# MCU.net
KiCad netlist of a schematic drawn in Altium Designer
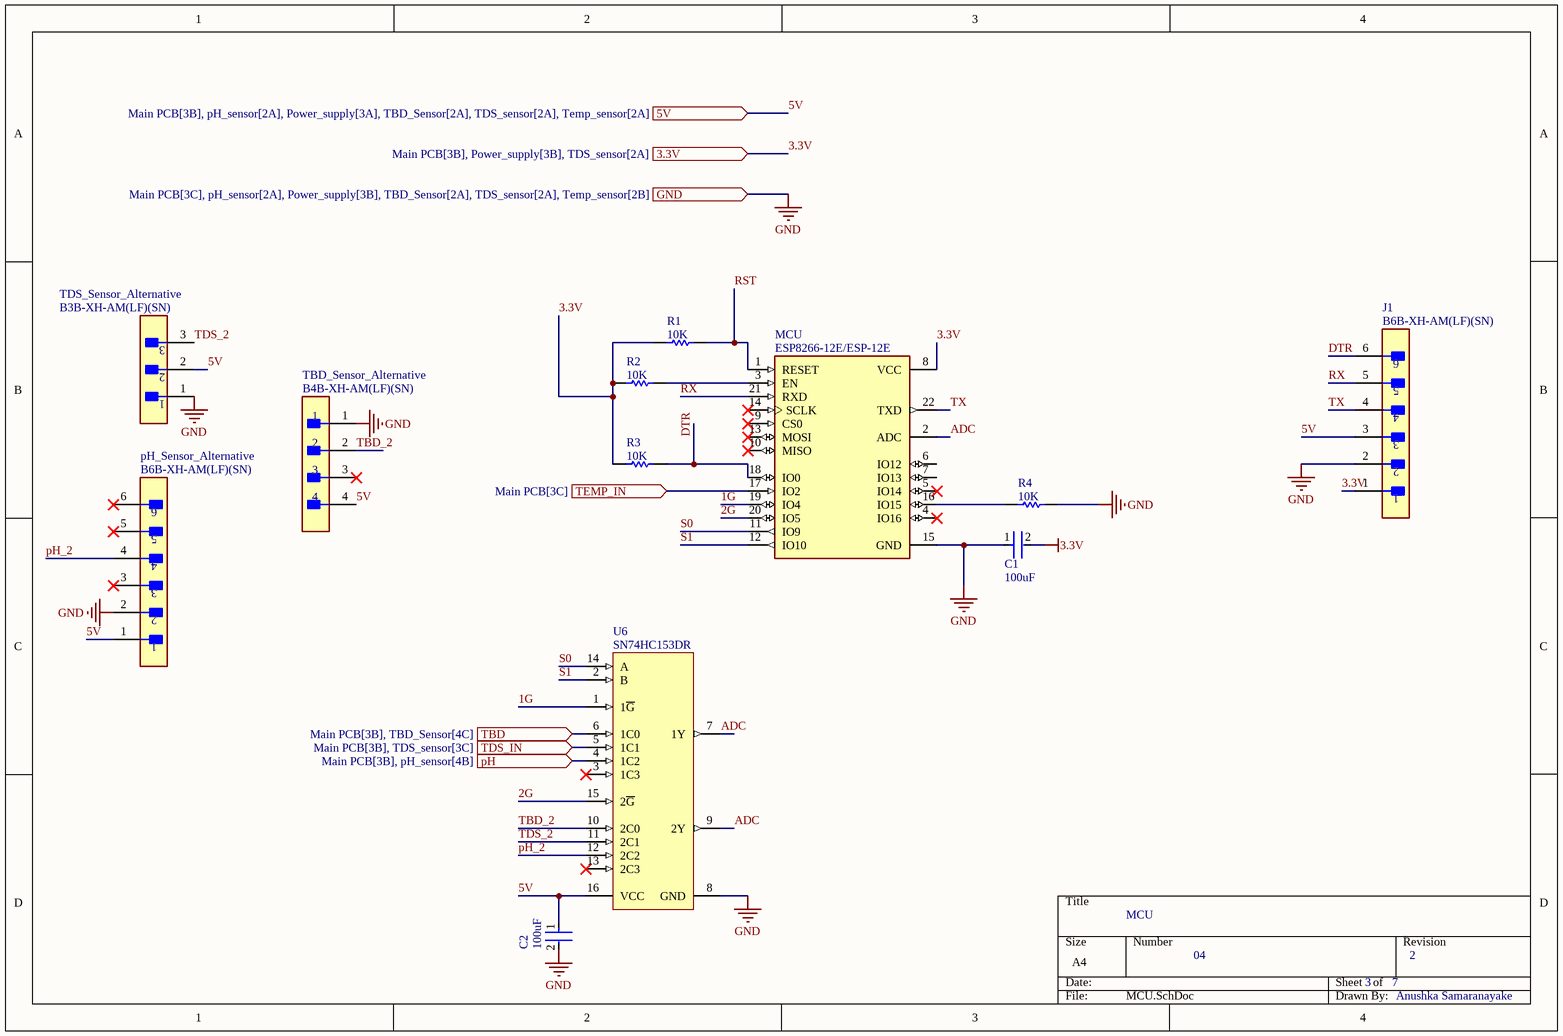
[diagram p0: MCU.SchDoc]

(export (version "E")
  (design (tool "Eeschema 10.0.6"))
  (components
    (comp (ref "C1")
      (value "100uF")
      (footprint "FP-GRM31M-0_15-IPC_A")
      (fields (field (name "VOLTAGE") "50V") (field (name "TOLERANCE") "5%"))
      (libsource (lib "Altium Content Vault") (part "b4654b650e69147ec39a6b967a45e02"))
    )
    (comp (ref "C2")
      (value "100uF")
      (footprint "FP-CL31-IPC_B")
      (description "Cap Ceramic 100nF 50V X7R ±10% SMD 1206 +125°C Embossed T/R")
      (fields (field (name "VOLTAGE") "50V") (field (name "TOLERANCE") "10%"))
      (libsource (lib "Altium Content Vault") (part "b4654b650e69147ec39a6b967a45e02"))
    )
    (comp (ref "J1")
      (value "B6B-XH-AM(LF)(SN)")
      (footprint "FP-B6B-XH-AM_LF_SN-MFG")
      (description "CONN HEADER VERT 6POS 2.5MM")
      (libsource (lib "Altium Content Vault") (part "f2cb566baf1c37ab5a3b8e90bbeafd6"))
    )
    (comp (ref "MCU")
      (value "ESP8266-12E/ESP-12E")
      (footprint "XCVR_ESP8266-12E/ESP-12E")
      (fields (field (name "MF") "AI-Thinker"))
      (libsource (lib "ESP8266-12E_ESP-12E") (part "ESP8266-12E/ESP-12E"))
    )
    (comp (ref "pH_Sensor_Alternative")
      (value "B6B-XH-AM(LF)(SN)")
      (footprint "FP-B6B-XH-AM_LF_SN-MFG")
      (description "CONN HEADER VERT 6POS 2.5MM")
      (libsource (lib "Altium Content Vault") (part "f2cb566baf1c37ab5a3b8e90bbeafd6"))
    )
    (comp (ref "R1")
      (value "10K")
      (footprint "RESC3216X70X50LL20T25")
      (fields (field (name "MANUFACTURER") "Panasonic") (field (name "PART NUMBER") "ERA8AEB103V"))
      (libsource (lib "Altium Content Vault") (part "RES"))
    )
    (comp (ref "R2")
      (value "10K")
      (footprint "RESC3216X70X50LL20T25")
      (fields (field (name "MANUFACTURER") "Panasonic") (field (name "PART NUMBER") "ERA8AEB103V"))
      (libsource (lib "Altium Content Vault") (part "RES"))
    )
    (comp (ref "R3")
      (value "10K")
      (footprint "RESC3216X70X50LL20T25")
      (fields (field (name "MANUFACTURER") "Panasonic") (field (name "PART NUMBER") "ERA8AEB103V"))
      (libsource (lib "Altium Content Vault") (part "RES"))
    )
    (comp (ref "R4")
      (value "10K")
      (footprint "RESC3216X70X50LL20T25")
      (fields (field (name "MANUFACTURER") "Panasonic") (field (name "PART NUMBER") "ERA8AEB103V"))
      (libsource (lib "Altium Content Vault") (part "RES"))
    )
    (comp (ref "TBD_Sensor_Alternative")
      (value "B4B-XH-AM(LF)(SN)")
      (footprint "FP-B4B-XH-AM_LF_SN-MFG")
      (description "CONN HEADER VERT 4POS 2.5MM")
      (libsource (lib "Altium Content Vault") (part "299a8cea1bdcbc3624fe62c390fa72c"))
    )
    (comp (ref "TDS_Sensor_Alternative")
      (value "B3B-XH-AM(LF)(SN)")
      (footprint "FP-B3B-XH-AM_LF_SN-MFG")
      (description "CONN HEADER VERT 3POS 2.5MM")
      (libsource (lib "Altium Content Vault") (part "0d3f023dd272f625e17a2be33dea85f"))
    )
    (comp (ref "U6")
      (value "SN74HC153DR")
      (footprint "D0016A_L")
      (description "Dual 4-Line To 1-Line Data Selectors/Multiplexers, D0016A, LARGE T&R")
      (fields
        (field (name "MANUFACTURER") "Texas Instruments")
        (field (name "GENERIC PART NUMBER") "SN74HC153")
      )
      (libsource (lib "Altium Content Vault") (part "TI-XXXXXXX153-16"))
    )
  )
  (nets
    (net (code "1") (name "/1G") (class "Default")
      (node (ref "MCU") (pin "19") (pinfunction "IO4_19") (pintype "bidirectional"))
      (node (ref "U6") (pin "1") (pinfunction "1~{G}_1") (pintype "input"))
    )
    (net (code "2") (name "/2G") (class "Default")
      (node (ref "MCU") (pin "20") (pinfunction "IO5_20") (pintype "bidirectional"))
      (node (ref "U6") (pin "15") (pinfunction "2~{G}_15") (pintype "input"))
    )
    (net (code "3") (name "/5V") (class "Default")
      (node (ref "C2") (pin "1") (pinfunction "1_1") (pintype "passive"))
      (node (ref "J1") (pin "3") (pinfunction "3_3") (pintype "passive"))
      (node (ref "TBD_Sensor_Alternative") (pin "4") (pinfunction "4_4") (pintype "passive"))
      (node (ref "TDS_Sensor_Alternative") (pin "2") (pinfunction "2_2") (pintype "passive"))
      (node (ref "U6") (pin "16") (pinfunction "VCC_16") (pintype "passive"))
      (node (ref "pH_Sensor_Alternative") (pin "1") (pinfunction "1_1") (pintype "passive"))
    )
    (net (code "4") (name "/ADC") (class "Default")
      (node (ref "MCU") (pin "2") (pinfunction "ADC_2") (pintype "passive"))
      (node (ref "U6") (pin "7") (pinfunction "1Y_7") (pintype "output"))
      (node (ref "U6") (pin "9") (pinfunction "2Y_9") (pintype "output"))
    )
    (net (code "5") (name "/DTR") (class "Default")
      (node (ref "J1") (pin "6") (pinfunction "6_6") (pintype "passive"))
      (node (ref "MCU") (pin "18") (pinfunction "IO0_18") (pintype "bidirectional"))
      (node (ref "R3") (pin "1") (pinfunction "1_1") (pintype "passive"))
    )
    (net (code "6") (name "/RST") (class "Default")
      (node (ref "MCU") (pin "1") (pinfunction "RESET_1") (pintype "input"))
      (node (ref "R1") (pin "1") (pinfunction "1_1") (pintype "passive"))
    )
    (net (code "7") (name "/RX") (class "Default")
      (node (ref "J1") (pin "5") (pinfunction "5_5") (pintype "passive"))
      (node (ref "MCU") (pin "21") (pinfunction "RXD_21") (pintype "input"))
    )
    (net (code "8") (name "/S0") (class "Default")
      (node (ref "MCU") (pin "11") (pinfunction "IO9_11") (pintype "output"))
      (node (ref "U6") (pin "14") (pinfunction "A_14") (pintype "input"))
    )
    (net (code "9") (name "/S1") (class "Default")
      (node (ref "MCU") (pin "12") (pinfunction "IO10_12") (pintype "output"))
      (node (ref "U6") (pin "2") (pinfunction "B_2") (pintype "input"))
    )
    (net (code "10") (name "/TBD") (class "Default")
      (node (ref "U6") (pin "6") (pinfunction "1C0_6") (pintype "input"))
    )
    (net (code "11") (name "/TBD_2") (class "Default")
      (node (ref "TBD_Sensor_Alternative") (pin "2") (pinfunction "2_2") (pintype "passive"))
      (node (ref "U6") (pin "10") (pinfunction "2C0_10") (pintype "input"))
    )
    (net (code "12") (name "/TDS_2") (class "Default")
      (node (ref "TDS_Sensor_Alternative") (pin "3") (pinfunction "3_3") (pintype "passive"))
      (node (ref "U6") (pin "11") (pinfunction "2C1_11") (pintype "input"))
    )
    (net (code "13") (name "/TDS_IN") (class "Default")
      (node (ref "U6") (pin "5") (pinfunction "1C1_5") (pintype "input"))
    )
    (net (code "14") (name "/TEMP_IN") (class "Default")
      (node (ref "MCU") (pin "17") (pinfunction "IO2_17") (pintype "input"))
    )
    (net (code "15") (name "/TX") (class "Default")
      (node (ref "J1") (pin "4") (pinfunction "4_4") (pintype "passive"))
      (node (ref "MCU") (pin "22") (pinfunction "TXD_22") (pintype "output"))
    )
    (net (code "16") (name "/pH") (class "Default")
      (node (ref "U6") (pin "4") (pinfunction "1C2_4") (pintype "input"))
    )
    (net (code "17") (name "/pH_2") (class "Default")
      (node (ref "U6") (pin "12") (pinfunction "2C2_12") (pintype "input"))
      (node (ref "pH_Sensor_Alternative") (pin "4") (pinfunction "4_4") (pintype "passive"))
    )
    (net (code "18") (name "3.3V") (class "Default")
      (node (ref "C1") (pin "2") (pinfunction "2_2") (pintype "passive"))
      (node (ref "J1") (pin "1") (pinfunction "1_1") (pintype "passive"))
      (node (ref "MCU") (pin "8") (pinfunction "VCC_8") (pintype "passive"))
      (node (ref "R1") (pin "2") (pinfunction "2_2") (pintype "passive"))
      (node (ref "R2") (pin "2") (pinfunction "2_2") (pintype "passive"))
      (node (ref "R3") (pin "2") (pinfunction "2_2") (pintype "passive"))
    )
    (net (code "19") (name "GND") (class "Default")
      (node (ref "C1") (pin "1") (pinfunction "1_1") (pintype "passive"))
      (node (ref "C2") (pin "2") (pinfunction "2_2") (pintype "passive"))
      (node (ref "J1") (pin "2") (pinfunction "2_2") (pintype "passive"))
      (node (ref "MCU") (pin "15") (pinfunction "GND_15") (pintype "passive"))
      (node (ref "R4") (pin "1") (pinfunction "1_1") (pintype "passive"))
      (node (ref "TBD_Sensor_Alternative") (pin "1") (pinfunction "1_1") (pintype "passive"))
      (node (ref "TDS_Sensor_Alternative") (pin "1") (pinfunction "1_1") (pintype "passive"))
      (node (ref "U6") (pin "8") (pinfunction "GND_8") (pintype "passive"))
      (node (ref "pH_Sensor_Alternative") (pin "2") (pinfunction "2_2") (pintype "passive"))
    )
    (net (code "20") (name "Net-(MCU-EN)") (class "Default")
      (node (ref "MCU") (pin "3") (pinfunction "EN_3") (pintype "input"))
      (node (ref "R2") (pin "1") (pinfunction "1_1") (pintype "passive"))
    )
    (net (code "21") (name "Net-(MCU-IO15)") (class "Default")
      (node (ref "MCU") (pin "16") (pinfunction "IO15_16") (pintype "bidirectional"))
      (node (ref "R4") (pin "2") (pinfunction "2_2") (pintype "passive"))
    )
    (net (code "22") (name "unconnected-(MCU-CS0-Pad9)") (class "Default")
      (node (ref "MCU") (pin "9") (pinfunction "CS0_9") (pintype "input+no_connect"))
    )
    (net (code "23") (name "unconnected-(MCU-IO12-Pad6)") (class "Default")
      (node (ref "MCU") (pin "6") (pinfunction "IO12_6") (pintype "bidirectional"))
    )
    (net (code "24") (name "unconnected-(MCU-IO13-Pad7)") (class "Default")
      (node (ref "MCU") (pin "7") (pinfunction "IO13_7") (pintype "bidirectional"))
    )
    (net (code "25") (name "unconnected-(MCU-IO14-Pad5)") (class "Default")
      (node (ref "MCU") (pin "5") (pinfunction "IO14_5") (pintype "bidirectional+no_connect"))
    )
    (net (code "26") (name "unconnected-(MCU-IO16-Pad4)") (class "Default")
      (node (ref "MCU") (pin "4") (pinfunction "IO16_4") (pintype "bidirectional+no_connect"))
    )
    (net (code "27") (name "unconnected-(MCU-MISO-Pad10)") (class "Default")
      (node (ref "MCU") (pin "10") (pinfunction "MISO_10") (pintype "bidirectional+no_connect"))
    )
    (net (code "28") (name "unconnected-(MCU-MOSI-Pad13)") (class "Default")
      (node (ref "MCU") (pin "13") (pinfunction "MOSI_13") (pintype "bidirectional+no_connect"))
    )
    (net (code "29") (name "unconnected-(MCU-SCLK-Pad14)") (class "Default")
      (node (ref "MCU") (pin "14") (pinfunction "SCLK_14") (pintype "input+no_connect"))
    )
    (net (code "30") (name "unconnected-(TBD_Sensor_Alternative-Pad3)") (class "Default")
      (node (ref "TBD_Sensor_Alternative") (pin "3") (pinfunction "3_3") (pintype "passive+no_connect"))
    )
    (net (code "31") (name "unconnected-(U6-1C3-Pad3)") (class "Default")
      (node (ref "U6") (pin "3") (pinfunction "1C3_3") (pintype "input+no_connect"))
    )
    (net (code "32") (name "unconnected-(U6-2C3-Pad13)") (class "Default")
      (node (ref "U6") (pin "13") (pinfunction "2C3_13") (pintype "input+no_connect"))
    )
    (net (code "33") (name "unconnected-(pH_Sensor_Alternative-Pad3)") (class "Default")
      (node (ref "pH_Sensor_Alternative") (pin "3") (pinfunction "3_3") (pintype "passive+no_connect"))
    )
    (net (code "34") (name "unconnected-(pH_Sensor_Alternative-Pad5)") (class "Default")
      (node (ref "pH_Sensor_Alternative") (pin "5") (pinfunction "5_5") (pintype "passive+no_connect"))
    )
    (net (code "35") (name "unconnected-(pH_Sensor_Alternative-Pad6)") (class "Default")
      (node (ref "pH_Sensor_Alternative") (pin "6") (pinfunction "6_6") (pintype "passive+no_connect"))
    )
  )
)
